# zulu_a7_6.net
KiCad netlist of a schematic drawn in Altium Designer
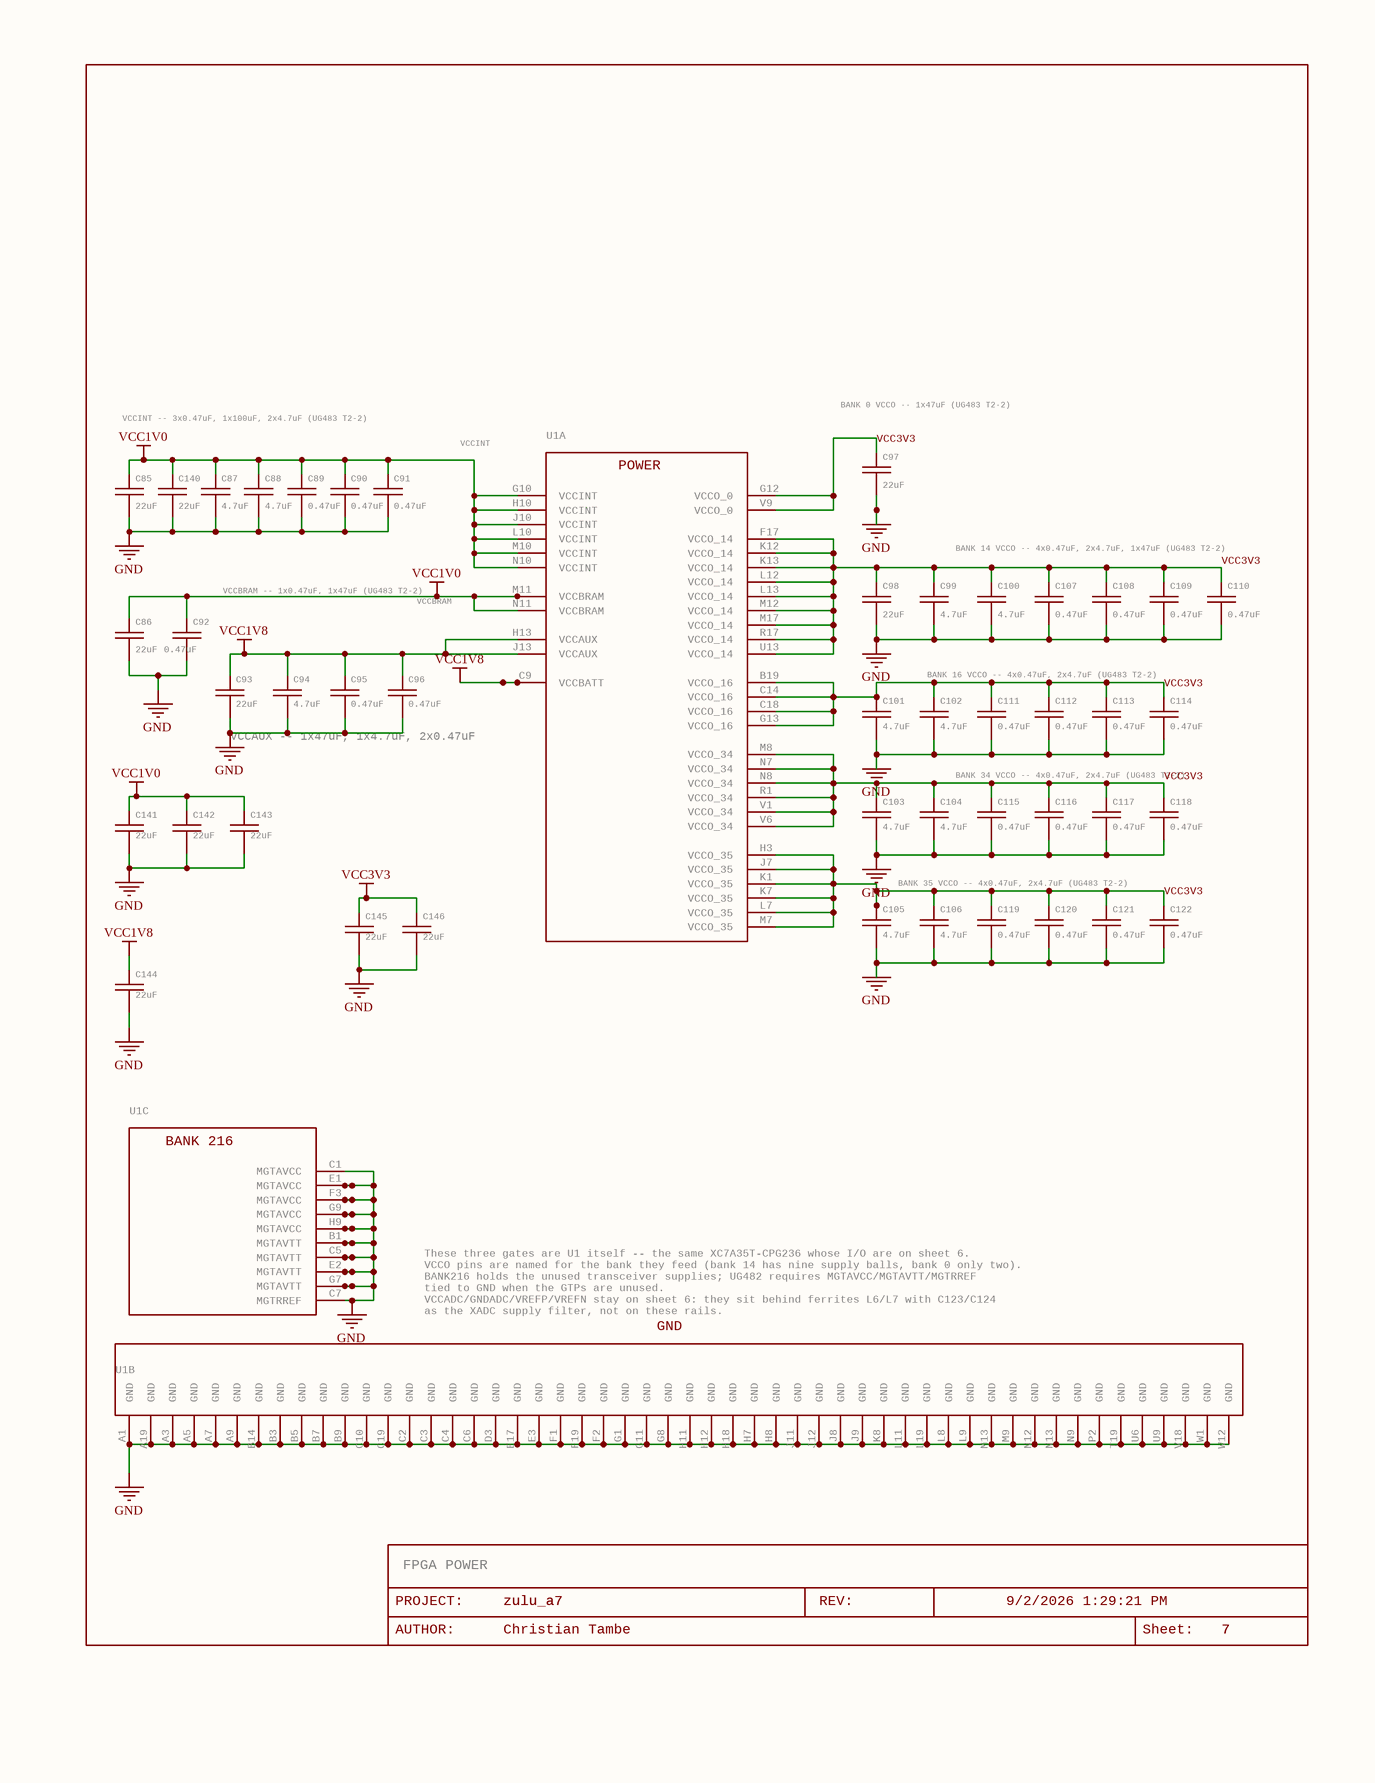
[diagram p0: zulu_a7_6.SchDoc]

(export (version "E")
  (design (tool "Eeschema 10.0.6"))
  (components
    (comp (ref "C85")
      (value "22uF")
      (footprint "C0805")
      (description "CAPACITOR, American symbol")
      (fields (field (name "MANF") "Murata"))
      (libsource (lib "rcl") (part "C-USC0805"))
    )
    (comp (ref "C86")
      (value "22uF")
      (footprint "C0805")
      (description "CAPACITOR, American symbol")
      (fields (field (name "MANF") "Murata"))
      (libsource (lib "rcl") (part "C-USC0805"))
    )
    (comp (ref "C87")
      (value "4.7uF")
      (footprint "C0603")
      (description "CAPACITOR, American symbol")
      (fields (field (name "MANF") "Murata"))
      (libsource (lib "rcl") (part "C-USC0603"))
    )
    (comp (ref "C88")
      (value "4.7uF")
      (footprint "C0603")
      (description "CAPACITOR, American symbol")
      (fields (field (name "MANF") "Murata"))
      (libsource (lib "rcl") (part "C-USC0603"))
    )
    (comp (ref "C89")
      (value "0.47uF")
      (footprint "C0201")
      (description "CAPACITOR, American symbol")
      (fields (field (name "MANF") "Murata"))
      (libsource (lib "rcl") (part "C-USC0201"))
    )
    (comp (ref "C90")
      (value "0.47uF")
      (footprint "C0201")
      (description "CAPACITOR, American symbol")
      (fields (field (name "MANF") "Murata"))
      (libsource (lib "rcl") (part "C-USC0201"))
    )
    (comp (ref "C91")
      (value "0.47uF")
      (footprint "C0201")
      (description "CAPACITOR, American symbol")
      (fields (field (name "MANF") "Murata"))
      (libsource (lib "rcl") (part "C-USC0201"))
    )
    (comp (ref "C92")
      (value "0.47uF")
      (footprint "C0201")
      (description "CAPACITOR, American symbol")
      (fields (field (name "MANF") "Murata"))
      (libsource (lib "rcl") (part "C-USC0201"))
    )
    (comp (ref "C93")
      (value "22uF")
      (footprint "C0805")
      (description "CAPACITOR, American symbol")
      (fields (field (name "MANF") "Murata"))
      (libsource (lib "rcl") (part "C-USC0805"))
    )
    (comp (ref "C94")
      (value "4.7uF")
      (footprint "C0603")
      (description "CAPACITOR, American symbol")
      (fields (field (name "MANF") "Murata"))
      (libsource (lib "rcl") (part "C-USC0603"))
    )
    (comp (ref "C95")
      (value "0.47uF")
      (footprint "C0201")
      (description "CAPACITOR, American symbol")
      (fields (field (name "MANF") "Murata"))
      (libsource (lib "rcl") (part "C-USC0201"))
    )
    (comp (ref "C96")
      (value "0.47uF")
      (footprint "C0201")
      (description "CAPACITOR, American symbol")
      (fields (field (name "MANF") "Murata"))
      (libsource (lib "rcl") (part "C-USC0201"))
    )
    (comp (ref "C97")
      (value "22uF")
      (footprint "C0805")
      (description "CAPACITOR, American symbol")
      (fields (field (name "MANF") "Murata"))
      (libsource (lib "rcl") (part "C-USC0805"))
    )
    (comp (ref "C98")
      (value "22uF")
      (footprint "C0805")
      (description "CAPACITOR, American symbol")
      (fields (field (name "MANF") "Murata"))
      (libsource (lib "rcl") (part "C-USC0805"))
    )
    (comp (ref "C99")
      (value "4.7uF")
      (footprint "C0603")
      (description "CAPACITOR, American symbol")
      (fields (field (name "MANF") "Murata"))
      (libsource (lib "rcl") (part "C-USC0603"))
    )
    (comp (ref "C100")
      (value "4.7uF")
      (footprint "C0603")
      (description "CAPACITOR, American symbol")
      (fields (field (name "MANF") "Murata"))
      (libsource (lib "rcl") (part "C-USC0603"))
    )
    (comp (ref "C101")
      (value "4.7uF")
      (footprint "C0603")
      (description "CAPACITOR, American symbol")
      (fields (field (name "MANF") "Murata"))
      (libsource (lib "rcl") (part "C-USC0603"))
    )
    (comp (ref "C102")
      (value "4.7uF")
      (footprint "C0603")
      (description "CAPACITOR, American symbol")
      (fields (field (name "MANF") "Murata"))
      (libsource (lib "rcl") (part "C-USC0603"))
    )
    (comp (ref "C103")
      (value "4.7uF")
      (footprint "C0603")
      (description "CAPACITOR, American symbol")
      (fields (field (name "MANF") "Murata"))
      (libsource (lib "rcl") (part "C-USC0603"))
    )
    (comp (ref "C104")
      (value "4.7uF")
      (footprint "C0603")
      (description "CAPACITOR, American symbol")
      (fields (field (name "MANF") "Murata"))
      (libsource (lib "rcl") (part "C-USC0603"))
    )
    (comp (ref "C105")
      (value "4.7uF")
      (footprint "C0603")
      (description "CAPACITOR, American symbol")
      (fields (field (name "MANF") "Murata"))
      (libsource (lib "rcl") (part "C-USC0603"))
    )
    (comp (ref "C106")
      (value "4.7uF")
      (footprint "C0603")
      (description "CAPACITOR, American symbol")
      (fields (field (name "MANF") "Murata"))
      (libsource (lib "rcl") (part "C-USC0603"))
    )
    (comp (ref "C107")
      (value "0.47uF")
      (footprint "C0201")
      (description "CAPACITOR, American symbol")
      (fields (field (name "MANF") "Murata"))
      (libsource (lib "rcl") (part "C-USC0201"))
    )
    (comp (ref "C108")
      (value "0.47uF")
      (footprint "C0201")
      (description "CAPACITOR, American symbol")
      (fields (field (name "MANF") "Murata"))
      (libsource (lib "rcl") (part "C-USC0201"))
    )
    (comp (ref "C109")
      (value "0.47uF")
      (footprint "C0201")
      (description "CAPACITOR, American symbol")
      (fields (field (name "MANF") "Murata"))
      (libsource (lib "rcl") (part "C-USC0201"))
    )
    (comp (ref "C110")
      (value "0.47uF")
      (footprint "C0201")
      (description "CAPACITOR, American symbol")
      (fields (field (name "MANF") "Murata"))
      (libsource (lib "rcl") (part "C-USC0201"))
    )
    (comp (ref "C111")
      (value "0.47uF")
      (footprint "C0201")
      (description "CAPACITOR, American symbol")
      (fields (field (name "MANF") "Murata"))
      (libsource (lib "rcl") (part "C-USC0201"))
    )
    (comp (ref "C112")
      (value "0.47uF")
      (footprint "C0201")
      (description "CAPACITOR, American symbol")
      (fields (field (name "MANF") "Murata"))
      (libsource (lib "rcl") (part "C-USC0201"))
    )
    (comp (ref "C113")
      (value "0.47uF")
      (footprint "C0201")
      (description "CAPACITOR, American symbol")
      (fields (field (name "MANF") "Murata"))
      (libsource (lib "rcl") (part "C-USC0201"))
    )
    (comp (ref "C114")
      (value "0.47uF")
      (footprint "C0201")
      (description "CAPACITOR, American symbol")
      (fields (field (name "MANF") "Murata"))
      (libsource (lib "rcl") (part "C-USC0201"))
    )
    (comp (ref "C115")
      (value "0.47uF")
      (footprint "C0201")
      (description "CAPACITOR, American symbol")
      (fields (field (name "MANF") "Murata"))
      (libsource (lib "rcl") (part "C-USC0201"))
    )
    (comp (ref "C116")
      (value "0.47uF")
      (footprint "C0201")
      (description "CAPACITOR, American symbol")
      (fields (field (name "MANF") "Murata"))
      (libsource (lib "rcl") (part "C-USC0201"))
    )
    (comp (ref "C117")
      (value "0.47uF")
      (footprint "C0201")
      (description "CAPACITOR, American symbol")
      (fields (field (name "MANF") "Murata"))
      (libsource (lib "rcl") (part "C-USC0201"))
    )
    (comp (ref "C118")
      (value "0.47uF")
      (footprint "C0201")
      (description "CAPACITOR, American symbol")
      (fields (field (name "MANF") "Murata"))
      (libsource (lib "rcl") (part "C-USC0201"))
    )
    (comp (ref "C119")
      (value "0.47uF")
      (footprint "C0201")
      (description "CAPACITOR, American symbol")
      (fields (field (name "MANF") "Murata"))
      (libsource (lib "rcl") (part "C-USC0201"))
    )
    (comp (ref "C120")
      (value "0.47uF")
      (footprint "C0201")
      (description "CAPACITOR, American symbol")
      (fields (field (name "MANF") "Murata"))
      (libsource (lib "rcl") (part "C-USC0201"))
    )
    (comp (ref "C121")
      (value "0.47uF")
      (footprint "C0201")
      (description "CAPACITOR, American symbol")
      (fields (field (name "MANF") "Murata"))
      (libsource (lib "rcl") (part "C-USC0201"))
    )
    (comp (ref "C122")
      (value "0.47uF")
      (footprint "C0201")
      (description "CAPACITOR, American symbol")
      (fields (field (name "MANF") "Murata"))
      (libsource (lib "rcl") (part "C-USC0201"))
    )
    (comp (ref "C140")
      (value "22uF")
      (footprint "C0805")
      (description "CAPACITOR, American symbol")
      (fields (field (name "MANF") "Murata"))
      (libsource (lib "rcl") (part "C-USC0805"))
    )
    (comp (ref "C141")
      (value "22uF")
      (footprint "C0805")
      (description "CAPACITOR, American symbol")
      (fields (field (name "MANF") "Murata"))
      (libsource (lib "rcl") (part "C-USC0805"))
    )
    (comp (ref "C142")
      (value "22uF")
      (footprint "C0805")
      (description "CAPACITOR, American symbol")
      (fields (field (name "MANF") "Murata"))
      (libsource (lib "rcl") (part "C-USC0805"))
    )
    (comp (ref "C143")
      (value "22uF")
      (footprint "C0805")
      (description "CAPACITOR, American symbol")
      (fields (field (name "MANF") "Murata"))
      (libsource (lib "rcl") (part "C-USC0805"))
    )
    (comp (ref "C144")
      (value "22uF")
      (footprint "C0805")
      (description "CAPACITOR, American symbol")
      (fields (field (name "MANF") "Murata"))
      (libsource (lib "") (part "C-USC0805_2"))
    )
    (comp (ref "C145")
      (value "22uF")
      (footprint "C0805")
      (description "CAPACITOR, American symbol")
      (fields (field (name "MANF") "Murata"))
      (libsource (lib "") (part "C-USC0805_1"))
    )
    (comp (ref "C146")
      (value "22uF")
      (footprint "C0805")
      (description "CAPACITOR, American symbol")
      (fields (field (name "MANF") "Murata"))
      (libsource (lib "") (part "C-USC0805_1"))
    )
    (comp (ref "FRAME6")
      (value "DOCFIELD")
      (description "DOCUMENT FIELD")
      (fields
        (field (name "LAST_DATE_TIME") "9/2/2026 1:29:21 PM")
        (field (name "SHEET") "Sheet:")
        (field (name "SHEET_1") "7")
        (field (name "REV") "REV:")
        (field (name "PROJECT") "PROJECT:")
        (field (name "DRAWING_NAME") "zulu_a7")
        (field (name "AUTHOR") "Christian Tambe")
        (field (name "DRAWING_NAME_1") "zulu_a7")
        (field (name "SHEET_2") "7")
        (field (name "LIBRARYNAME") "ctambe")
      )
      (libsource (lib "ctambe") (part "DOCFIELD"))
    )
    (comp (ref "U1")
      (value "XC7A35T-1CPG236C")
      (footprint "XC7A35T-CPG236")
      (fields
        (field (name "BANK216") "BANK 216")
        (field (name "MANF") "AMD/Xilinx")
        (field (name "GND") "GND")
        (field (name "POWER") "POWER")
        (field (name "LIBRARYNAME") "ctambe")
      )
      (libsource (lib "ctambe") (part "XC7A35T-CPG236-1CPG236C"))
    )
  )
  (nets
    (net (code "1") (name "GND") (class "Default")
      (node (ref "C100") (pin "2") (pinfunction "2_2") (pintype "passive"))
      (node (ref "C101") (pin "2") (pinfunction "2_2") (pintype "passive"))
      (node (ref "C102") (pin "2") (pinfunction "2_2") (pintype "passive"))
      (node (ref "C103") (pin "2") (pinfunction "2_2") (pintype "passive"))
      (node (ref "C104") (pin "2") (pinfunction "2_2") (pintype "passive"))
      (node (ref "C105") (pin "2") (pinfunction "2_2") (pintype "passive"))
      (node (ref "C106") (pin "2") (pinfunction "2_2") (pintype "passive"))
      (node (ref "C107") (pin "2") (pinfunction "2_2") (pintype "passive"))
      (node (ref "C108") (pin "2") (pinfunction "2_2") (pintype "passive"))
      (node (ref "C109") (pin "2") (pinfunction "2_2") (pintype "passive"))
      (node (ref "C110") (pin "2") (pinfunction "2_2") (pintype "passive"))
      (node (ref "C111") (pin "2") (pinfunction "2_2") (pintype "passive"))
      (node (ref "C112") (pin "2") (pinfunction "2_2") (pintype "passive"))
      (node (ref "C113") (pin "2") (pinfunction "2_2") (pintype "passive"))
      (node (ref "C114") (pin "2") (pinfunction "2_2") (pintype "passive"))
      (node (ref "C115") (pin "2") (pinfunction "2_2") (pintype "passive"))
      (node (ref "C116") (pin "2") (pinfunction "2_2") (pintype "passive"))
      (node (ref "C117") (pin "2") (pinfunction "2_2") (pintype "passive"))
      (node (ref "C118") (pin "2") (pinfunction "2_2") (pintype "passive"))
      (node (ref "C119") (pin "2") (pinfunction "2_2") (pintype "passive"))
      (node (ref "C120") (pin "2") (pinfunction "2_2") (pintype "passive"))
      (node (ref "C121") (pin "2") (pinfunction "2_2") (pintype "passive"))
      (node (ref "C122") (pin "2") (pinfunction "2_2") (pintype "passive"))
      (node (ref "C140") (pin "2") (pinfunction "2_2") (pintype "passive"))
      (node (ref "C141") (pin "2") (pinfunction "2_2") (pintype "passive"))
      (node (ref "C142") (pin "2") (pinfunction "2_2") (pintype "passive"))
      (node (ref "C143") (pin "2") (pinfunction "2_2") (pintype "passive"))
      (node (ref "C144") (pin "2") (pinfunction "2_2") (pintype "passive"))
      (node (ref "C145") (pin "2") (pinfunction "2_2") (pintype "passive"))
      (node (ref "C146") (pin "2") (pinfunction "2_2") (pintype "passive"))
      (node (ref "C85") (pin "2") (pinfunction "2_2") (pintype "passive"))
      (node (ref "C86") (pin "2") (pinfunction "2_2") (pintype "passive"))
      (node (ref "C87") (pin "2") (pinfunction "2_2") (pintype "passive"))
      (node (ref "C88") (pin "2") (pinfunction "2_2") (pintype "passive"))
      (node (ref "C89") (pin "2") (pinfunction "2_2") (pintype "passive"))
      (node (ref "C90") (pin "2") (pinfunction "2_2") (pintype "passive"))
      (node (ref "C91") (pin "2") (pinfunction "2_2") (pintype "passive"))
      (node (ref "C92") (pin "2") (pinfunction "2_2") (pintype "passive"))
      (node (ref "C93") (pin "2") (pinfunction "2_2") (pintype "passive"))
      (node (ref "C94") (pin "2") (pinfunction "2_2") (pintype "passive"))
      (node (ref "C95") (pin "2") (pinfunction "2_2") (pintype "passive"))
      (node (ref "C96") (pin "2") (pinfunction "2_2") (pintype "passive"))
      (node (ref "C97") (pin "2") (pinfunction "2_2") (pintype "passive"))
      (node (ref "C98") (pin "2") (pinfunction "2_2") (pintype "passive"))
      (node (ref "C99") (pin "2") (pinfunction "2_2") (pintype "passive"))
      (node (ref "U1") (pin "A1") (pinfunction "GND_A1") (pintype "power_in"))
      (node (ref "U1") (pin "A19") (pinfunction "GND_A19") (pintype "power_in"))
      (node (ref "U1") (pin "A3") (pinfunction "GND_A3") (pintype "power_in"))
      (node (ref "U1") (pin "A5") (pinfunction "GND_A5") (pintype "power_in"))
      (node (ref "U1") (pin "A7") (pinfunction "GND_A7") (pintype "power_in"))
      (node (ref "U1") (pin "A9") (pinfunction "GND_A9") (pintype "power_in"))
      (node (ref "U1") (pin "B1") (pinfunction "MGTAVTT_B1") (pintype "power_in"))
      (node (ref "U1") (pin "B14") (pinfunction "GND_B14") (pintype "power_in"))
      (node (ref "U1") (pin "B3") (pinfunction "GND_B3") (pintype "power_in"))
      (node (ref "U1") (pin "B5") (pinfunction "GND_B5") (pintype "power_in"))
      (node (ref "U1") (pin "B7") (pinfunction "GND_B7") (pintype "power_in"))
      (node (ref "U1") (pin "B9") (pinfunction "GND_B9") (pintype "power_in"))
      (node (ref "U1") (pin "C1") (pinfunction "MGTAVCC_C1") (pintype "power_in"))
      (node (ref "U1") (pin "C10") (pinfunction "GND_C10") (pintype "power_in"))
      (node (ref "U1") (pin "C19") (pinfunction "GND_C19") (pintype "power_in"))
      (node (ref "U1") (pin "C2") (pinfunction "GND_C2") (pintype "power_in"))
      (node (ref "U1") (pin "C3") (pinfunction "GND_C3") (pintype "power_in"))
      (node (ref "U1") (pin "C4") (pinfunction "GND_C4") (pintype "power_in"))
      (node (ref "U1") (pin "C5") (pinfunction "MGTAVTT_C5") (pintype "power_in"))
      (node (ref "U1") (pin "C6") (pinfunction "GND_C6") (pintype "power_in"))
      (node (ref "U1") (pin "C7") (pinfunction "MGTRREF_C7") (pintype "power_in"))
      (node (ref "U1") (pin "D3") (pinfunction "GND_D3") (pintype "power_in"))
      (node (ref "U1") (pin "E1") (pinfunction "MGTAVCC_E1") (pintype "power_in"))
      (node (ref "U1") (pin "E17") (pinfunction "GND_E17") (pintype "power_in"))
      (node (ref "U1") (pin "E2") (pinfunction "MGTAVTT_E2") (pintype "power_in"))
      (node (ref "U1") (pin "E3") (pinfunction "GND_E3") (pintype "power_in"))
      (node (ref "U1") (pin "F1") (pinfunction "GND_F1") (pintype "power_in"))
      (node (ref "U1") (pin "F19") (pinfunction "GND_F19") (pintype "power_in"))
      (node (ref "U1") (pin "F2") (pinfunction "GND_F2") (pintype "power_in"))
      (node (ref "U1") (pin "F3") (pinfunction "MGTAVCC_F3") (pintype "power_in"))
      (node (ref "U1") (pin "G1") (pinfunction "GND_G1") (pintype "power_in"))
      (node (ref "U1") (pin "G11") (pinfunction "GND_G11") (pintype "power_in"))
      (node (ref "U1") (pin "G7") (pinfunction "MGTAVTT_G7") (pintype "power_in"))
      (node (ref "U1") (pin "G8") (pinfunction "GND_G8") (pintype "power_in"))
      (node (ref "U1") (pin "G9") (pinfunction "MGTAVCC_G9") (pintype "power_in"))
      (node (ref "U1") (pin "H11") (pinfunction "GND_H11") (pintype "power_in"))
      (node (ref "U1") (pin "H12") (pinfunction "GND_H12") (pintype "power_in"))
      (node (ref "U1") (pin "H18") (pinfunction "GND_H18") (pintype "power_in"))
      (node (ref "U1") (pin "H7") (pinfunction "GND_H7") (pintype "power_in"))
      (node (ref "U1") (pin "H8") (pinfunction "GND_H8") (pintype "power_in"))
      (node (ref "U1") (pin "H9") (pinfunction "MGTAVCC_H9") (pintype "power_in"))
      (node (ref "U1") (pin "J11") (pinfunction "GND_J11") (pintype "power_in"))
      (node (ref "U1") (pin "J12") (pinfunction "GND_J12") (pintype "power_in"))
      (node (ref "U1") (pin "J8") (pinfunction "GND_J8") (pintype "power_in"))
      (node (ref "U1") (pin "J9") (pinfunction "GND_J9") (pintype "power_in"))
      (node (ref "U1") (pin "K8") (pinfunction "GND_K8") (pintype "power_in"))
      (node (ref "U1") (pin "L11") (pinfunction "GND_L11") (pintype "power_in"))
      (node (ref "U1") (pin "L19") (pinfunction "GND_L19") (pintype "power_in"))
      (node (ref "U1") (pin "L8") (pinfunction "GND_L8") (pintype "power_in"))
      (node (ref "U1") (pin "L9") (pinfunction "GND_L9") (pintype "power_in"))
      (node (ref "U1") (pin "M13") (pinfunction "GND_M13") (pintype "power_in"))
      (node (ref "U1") (pin "M9") (pinfunction "GND_M9") (pintype "power_in"))
      (node (ref "U1") (pin "N12") (pinfunction "GND_N12") (pintype "power_in"))
      (node (ref "U1") (pin "N13") (pinfunction "GND_N13") (pintype "power_in"))
      (node (ref "U1") (pin "N9") (pinfunction "GND_N9") (pintype "power_in"))
      (node (ref "U1") (pin "P2") (pinfunction "GND_P2") (pintype "power_in"))
      (node (ref "U1") (pin "T19") (pinfunction "GND_T19") (pintype "power_in"))
      (node (ref "U1") (pin "U6") (pinfunction "GND_U6") (pintype "power_in"))
      (node (ref "U1") (pin "U9") (pinfunction "GND_U9") (pintype "power_in"))
      (node (ref "U1") (pin "V18") (pinfunction "GND_V18") (pintype "power_in"))
      (node (ref "U1") (pin "W1") (pinfunction "GND_W1") (pintype "power_in"))
      (node (ref "U1") (pin "W12") (pinfunction "GND_W12") (pintype "power_in"))
    )
    (net (code "2") (name "VCC1V0") (class "Default")
      (node (ref "C140") (pin "1") (pinfunction "1_1") (pintype "passive"))
      (node (ref "C141") (pin "1") (pinfunction "1_1") (pintype "passive"))
      (node (ref "C142") (pin "1") (pinfunction "1_1") (pintype "passive"))
      (node (ref "C143") (pin "1") (pinfunction "1_1") (pintype "passive"))
      (node (ref "C85") (pin "1") (pinfunction "1_1") (pintype "passive"))
      (node (ref "C86") (pin "1") (pinfunction "1_1") (pintype "passive"))
      (node (ref "C87") (pin "1") (pinfunction "1_1") (pintype "passive"))
      (node (ref "C88") (pin "1") (pinfunction "1_1") (pintype "passive"))
      (node (ref "C89") (pin "1") (pinfunction "1_1") (pintype "passive"))
      (node (ref "C90") (pin "1") (pinfunction "1_1") (pintype "passive"))
      (node (ref "C91") (pin "1") (pinfunction "1_1") (pintype "passive"))
      (node (ref "C92") (pin "1") (pinfunction "1_1") (pintype "passive"))
      (node (ref "U1") (pin "G10") (pinfunction "VCCINT_G10") (pintype "power_in"))
      (node (ref "U1") (pin "H10") (pinfunction "VCCINT_H10") (pintype "power_in"))
      (node (ref "U1") (pin "J10") (pinfunction "VCCINT_J10") (pintype "power_in"))
      (node (ref "U1") (pin "L10") (pinfunction "VCCINT_L10") (pintype "power_in"))
      (node (ref "U1") (pin "M10") (pinfunction "VCCINT_M10") (pintype "power_in"))
      (node (ref "U1") (pin "M11") (pinfunction "VCCBRAM_M11") (pintype "power_in"))
      (node (ref "U1") (pin "N10") (pinfunction "VCCINT_N10") (pintype "power_in"))
      (node (ref "U1") (pin "N11") (pinfunction "VCCBRAM_N11") (pintype "power_in"))
    )
    (net (code "3") (name "VCC1V8") (class "Default")
      (node (ref "C144") (pin "1") (pinfunction "1_1") (pintype "passive"))
      (node (ref "C93") (pin "1") (pinfunction "1_1") (pintype "passive"))
      (node (ref "C94") (pin "1") (pinfunction "1_1") (pintype "passive"))
      (node (ref "C95") (pin "1") (pinfunction "1_1") (pintype "passive"))
      (node (ref "C96") (pin "1") (pinfunction "1_1") (pintype "passive"))
      (node (ref "U1") (pin "C9") (pinfunction "VCCBATT_C9") (pintype "power_in"))
      (node (ref "U1") (pin "H13") (pinfunction "VCCAUX_H13") (pintype "power_in"))
      (node (ref "U1") (pin "J13") (pinfunction "VCCAUX_J13") (pintype "power_in"))
    )
    (net (code "4") (name "VCC3V3") (class "Default")
      (node (ref "C100") (pin "1") (pinfunction "1_1") (pintype "passive"))
      (node (ref "C101") (pin "1") (pinfunction "1_1") (pintype "passive"))
      (node (ref "C102") (pin "1") (pinfunction "1_1") (pintype "passive"))
      (node (ref "C103") (pin "1") (pinfunction "1_1") (pintype "passive"))
      (node (ref "C104") (pin "1") (pinfunction "1_1") (pintype "passive"))
      (node (ref "C105") (pin "1") (pinfunction "1_1") (pintype "passive"))
      (node (ref "C106") (pin "1") (pinfunction "1_1") (pintype "passive"))
      (node (ref "C107") (pin "1") (pinfunction "1_1") (pintype "passive"))
      (node (ref "C108") (pin "1") (pinfunction "1_1") (pintype "passive"))
      (node (ref "C109") (pin "1") (pinfunction "1_1") (pintype "passive"))
      (node (ref "C110") (pin "1") (pinfunction "1_1") (pintype "passive"))
      (node (ref "C111") (pin "1") (pinfunction "1_1") (pintype "passive"))
      (node (ref "C112") (pin "1") (pinfunction "1_1") (pintype "passive"))
      (node (ref "C113") (pin "1") (pinfunction "1_1") (pintype "passive"))
      (node (ref "C114") (pin "1") (pinfunction "1_1") (pintype "passive"))
      (node (ref "C115") (pin "1") (pinfunction "1_1") (pintype "passive"))
      (node (ref "C116") (pin "1") (pinfunction "1_1") (pintype "passive"))
      (node (ref "C117") (pin "1") (pinfunction "1_1") (pintype "passive"))
      (node (ref "C118") (pin "1") (pinfunction "1_1") (pintype "passive"))
      (node (ref "C119") (pin "1") (pinfunction "1_1") (pintype "passive"))
      (node (ref "C120") (pin "1") (pinfunction "1_1") (pintype "passive"))
      (node (ref "C121") (pin "1") (pinfunction "1_1") (pintype "passive"))
      (node (ref "C122") (pin "1") (pinfunction "1_1") (pintype "passive"))
      (node (ref "C145") (pin "1") (pinfunction "1_1") (pintype "passive"))
      (node (ref "C146") (pin "1") (pinfunction "1_1") (pintype "passive"))
      (node (ref "C97") (pin "1") (pinfunction "1_1") (pintype "passive"))
      (node (ref "C98") (pin "1") (pinfunction "1_1") (pintype "passive"))
      (node (ref "C99") (pin "1") (pinfunction "1_1") (pintype "passive"))
      (node (ref "U1") (pin "B19") (pinfunction "VCCO_16_B19") (pintype "power_in"))
      (node (ref "U1") (pin "C14") (pinfunction "VCCO_16_C14") (pintype "power_in"))
      (node (ref "U1") (pin "C18") (pinfunction "VCCO_16_C18") (pintype "power_in"))
      (node (ref "U1") (pin "F17") (pinfunction "VCCO_14_F17") (pintype "power_in"))
      (node (ref "U1") (pin "G12") (pinfunction "VCCO_0_G12") (pintype "power_in"))
      (node (ref "U1") (pin "G13") (pinfunction "VCCO_16_G13") (pintype "power_in"))
      (node (ref "U1") (pin "H3") (pinfunction "VCCO_35_H3") (pintype "power_in"))
      (node (ref "U1") (pin "J7") (pinfunction "VCCO_35_J7") (pintype "power_in"))
      (node (ref "U1") (pin "K1") (pinfunction "VCCO_35_K1") (pintype "power_in"))
      (node (ref "U1") (pin "K12") (pinfunction "VCCO_14_K12") (pintype "power_in"))
      (node (ref "U1") (pin "K13") (pinfunction "VCCO_14_K13") (pintype "power_in"))
      (node (ref "U1") (pin "K7") (pinfunction "VCCO_35_K7") (pintype "power_in"))
      (node (ref "U1") (pin "L12") (pinfunction "VCCO_14_L12") (pintype "power_in"))
      (node (ref "U1") (pin "L13") (pinfunction "VCCO_14_L13") (pintype "power_in"))
      (node (ref "U1") (pin "L7") (pinfunction "VCCO_35_L7") (pintype "power_in"))
      (node (ref "U1") (pin "M12") (pinfunction "VCCO_14_M12") (pintype "power_in"))
      (node (ref "U1") (pin "M17") (pinfunction "VCCO_14_M17") (pintype "power_in"))
      (node (ref "U1") (pin "M7") (pinfunction "VCCO_35_M7") (pintype "power_in"))
      (node (ref "U1") (pin "M8") (pinfunction "VCCO_34_M8") (pintype "power_in"))
      (node (ref "U1") (pin "N7") (pinfunction "VCCO_34_N7") (pintype "power_in"))
      (node (ref "U1") (pin "N8") (pinfunction "VCCO_34_N8") (pintype "power_in"))
      (node (ref "U1") (pin "R1") (pinfunction "VCCO_34_R1") (pintype "power_in"))
      (node (ref "U1") (pin "R17") (pinfunction "VCCO_14_R17") (pintype "power_in"))
      (node (ref "U1") (pin "U13") (pinfunction "VCCO_14_U13") (pintype "power_in"))
      (node (ref "U1") (pin "V1") (pinfunction "VCCO_34_V1") (pintype "power_in"))
      (node (ref "U1") (pin "V6") (pinfunction "VCCO_34_V6") (pintype "power_in"))
      (node (ref "U1") (pin "V9") (pinfunction "VCCO_0_V9") (pintype "power_in"))
    )
  )
)
